# ArduinoWeatherStation.net
KiCad netlist of a schematic drawn in EAGLE
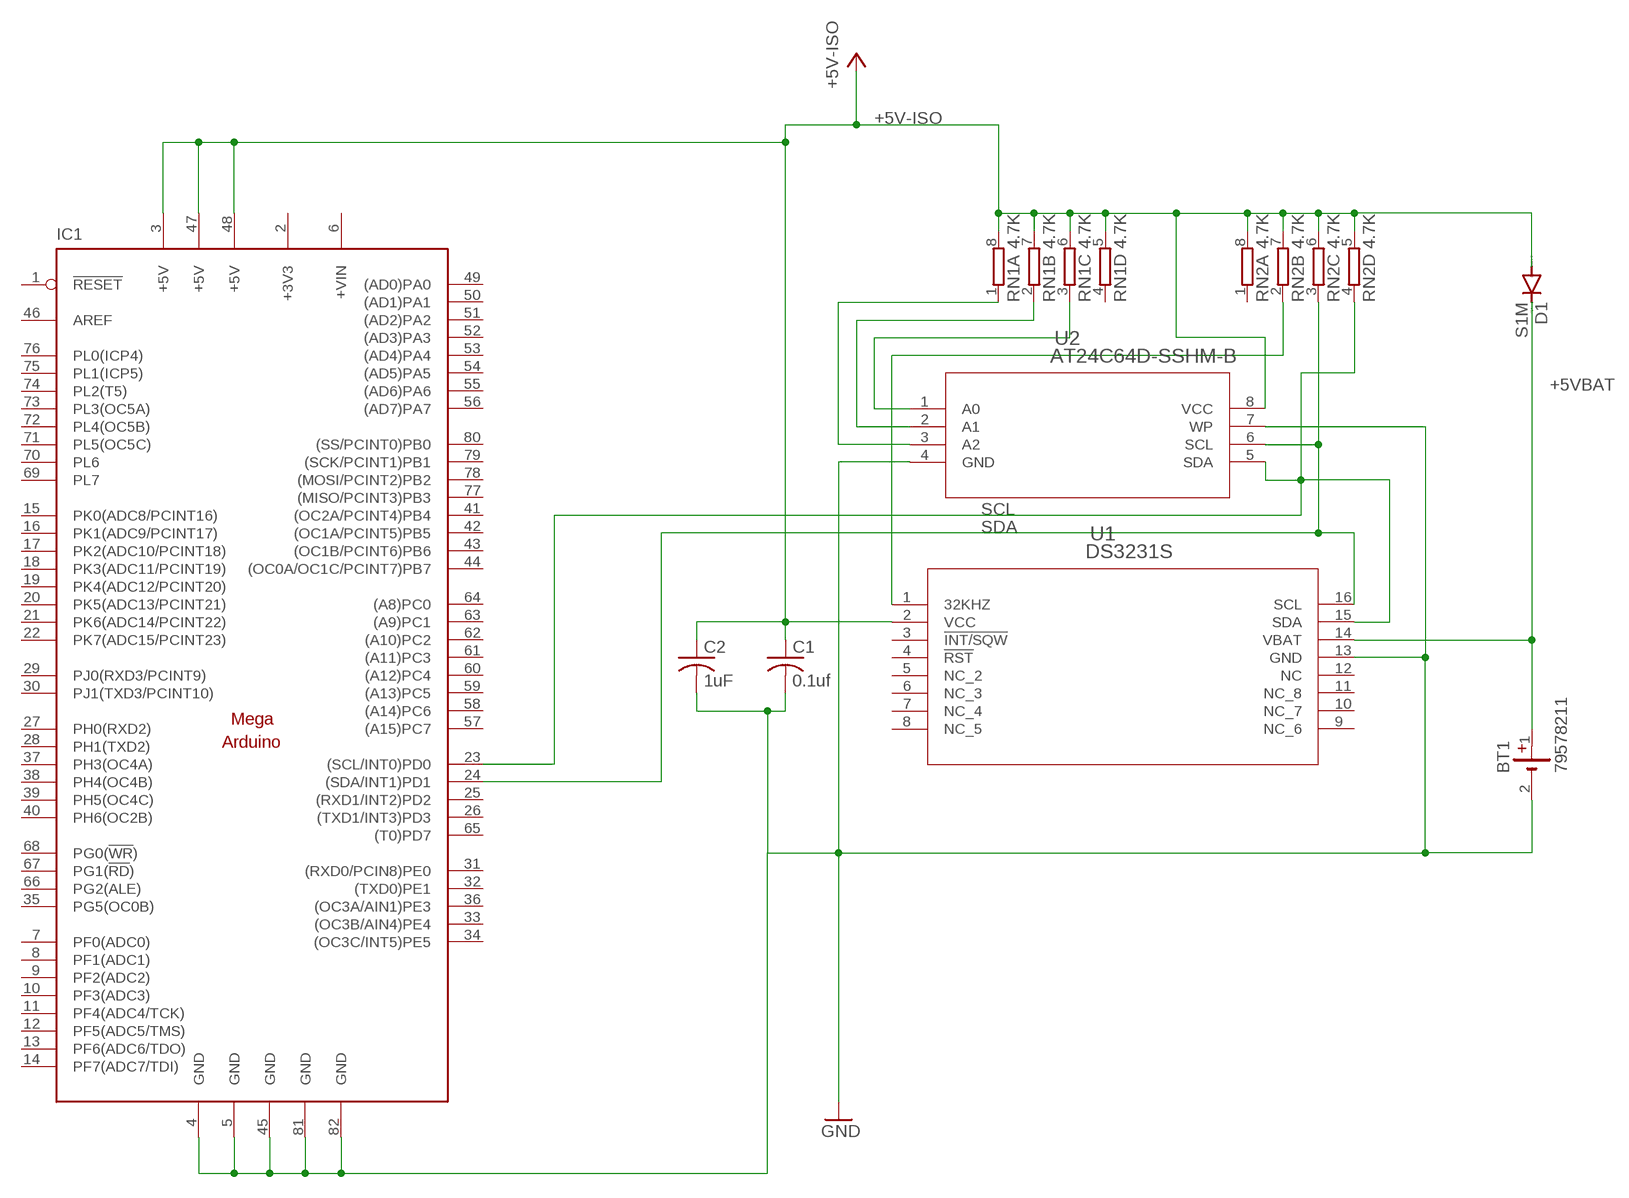
[diagram p0: schematic, sheet 1]

(export (version "E")
  (design (tool "Eeschema 10.0.6"))
  (components
    (comp (ref "BT1")
      (value "79578211")
      (footprint "eagle-import:79578211")
      (fields
        (field (name "DIGIKEY_PART_NO") "732-12330-ND")
        (field (name "MANUFACTURER") "Wurth Electronics Inc.")
        (field (name "CREATED_BY") "PCBLayout.com")
      )
      (libsource (lib "eagle-import") (part "79578211"))
    )
    (comp (ref "C1")
      (value "0.1uf")
      (footprint "eagle-import:C0603")
      (libsource (lib "eagle-import") (part "C-USC0603"))
    )
    (comp (ref "C2")
      (value "1uF")
      (footprint "eagle-import:C0603")
      (libsource (lib "eagle-import") (part "C-USC0603"))
    )
    (comp (ref "D1")
      (value "S1M")
      (footprint "eagle-import:SMA")
      (libsource (lib "eagle-import") (part "S1M"))
    )
    (comp (ref "IC1")
      (value "MEGAARDUINO_1")
      (footprint "eagle-import:MEGA_ARDUINO")
      (libsource (lib "eagle-import") (part "MEGAARDUINO_1"))
    )
    (comp (ref "RN1")
      (value "4.7K")
      (footprint "eagle-import:0603-ARC")
      (libsource (lib "eagle-import") (part "4R-N0603-ARC"))
    )
    (comp (ref "RN2")
      (value "4.7K")
      (footprint "eagle-import:0603-ARC")
      (libsource (lib "eagle-import") (part "4R-N0603-ARC"))
    )
    (comp (ref "U1")
      (value "DS3231S")
      (footprint "eagle-import:21-0042B_16")
      (libsource (lib "eagle-import") (part "DS3231S"))
    )
    (comp (ref "U2")
      (value "AT24C64D-SSHM-B")
      (footprint "eagle-import:8S1")
      (fields (field (name "MANUFACTURER_PART_NUMBER") "AT24C64DSSHMB"))
      (libsource (lib "eagle-import") (part "AT24C64D-SSHM-B"))
    )
  )
  (nets
    (net (code "1") (name "+5V-ISO") (class "Default")
      (node (ref "C1") (pin "1") (pinfunction "1_1") (pintype "passive"))
      (node (ref "C2") (pin "1") (pinfunction "1_1") (pintype "passive"))
      (node (ref "D1") (pin "A") (pinfunction "A_A") (pintype "passive"))
      (node (ref "IC1") (pin "3") (pinfunction "+5V_3") (pintype "power_in"))
      (node (ref "IC1") (pin "47") (pinfunction "+5V_47") (pintype "power_in"))
      (node (ref "IC1") (pin "48") (pinfunction "+5V_48") (pintype "power_in"))
      (node (ref "RN1") (pin "5") (pinfunction "2_5") (pintype "passive"))
      (node (ref "RN1") (pin "6") (pinfunction "2_6") (pintype "passive"))
      (node (ref "RN1") (pin "7") (pinfunction "2_7") (pintype "passive"))
      (node (ref "RN1") (pin "8") (pinfunction "2_8") (pintype "passive"))
      (node (ref "RN2") (pin "5") (pinfunction "2_5") (pintype "passive"))
      (node (ref "RN2") (pin "6") (pinfunction "2_6") (pintype "passive"))
      (node (ref "RN2") (pin "7") (pinfunction "2_7") (pintype "passive"))
      (node (ref "RN2") (pin "8") (pinfunction "2_8") (pintype "passive"))
      (node (ref "U1") (pin "2") (pinfunction "VCC_2") (pintype "power_in"))
      (node (ref "U2") (pin "8") (pinfunction "VCC_8") (pintype "power_in"))
    )
    (net (code "2") (name "/+3V3") (class "Default")
      (node (ref "IC1") (pin "2") (pinfunction "+3V3_2") (pintype "power_in"))
    )
    (net (code "3") (name "/+5VBAT") (class "Default")
      (node (ref "BT1") (pin "1") (pinfunction "+_1") (pintype "passive"))
      (node (ref "D1") (pin "C") (pinfunction "C_C") (pintype "passive"))
      (node (ref "U1") (pin "14") (pinfunction "VBAT_14") (pintype "power_in"))
    )
    (net (code "4") (name "/+VIN") (class "Default")
      (node (ref "IC1") (pin "6") (pinfunction "+VIN_6") (pintype "power_in"))
    )
    (net (code "5") (name "/SCL") (class "Default")
      (node (ref "IC1") (pin "23") (pinfunction "(SCL/INT0)PD0_23") (pintype "bidirectional"))
      (node (ref "RN2") (pin "4") (pinfunction "1_4") (pintype "passive"))
      (node (ref "U1") (pin "15") (pinfunction "SDA_15") (pintype "passive"))
      (node (ref "U2") (pin "5") (pinfunction "SDA_5") (pintype "passive"))
    )
    (net (code "6") (name "/SDA") (class "Default")
      (node (ref "IC1") (pin "24") (pinfunction "(SDA/INT1)PD1_24") (pintype "bidirectional"))
      (node (ref "RN2") (pin "3") (pinfunction "1_3") (pintype "passive"))
      (node (ref "U1") (pin "16") (pinfunction "SCL_16") (pintype "passive"))
      (node (ref "U2") (pin "6") (pinfunction "SCL_6") (pintype "input"))
    )
    (net (code "7") (name "GND") (class "Default")
      (node (ref "BT1") (pin "2") (pinfunction "-_2") (pintype "passive"))
      (node (ref "C1") (pin "2") (pinfunction "2_2") (pintype "passive"))
      (node (ref "C2") (pin "2") (pinfunction "2_2") (pintype "passive"))
      (node (ref "IC1") (pin "4") (pinfunction "GND_4") (pintype "power_in"))
      (node (ref "IC1") (pin "45") (pinfunction "GND_45") (pintype "power_in"))
      (node (ref "IC1") (pin "5") (pinfunction "GND_5") (pintype "power_in"))
      (node (ref "IC1") (pin "81") (pinfunction "GND_81") (pintype "power_in"))
      (node (ref "IC1") (pin "82") (pinfunction "GND_82") (pintype "power_in"))
      (node (ref "U1") (pin "13") (pinfunction "GND_13") (pintype "power_in"))
      (node (ref "U2") (pin "4") (pinfunction "GND_4") (pintype "power_in"))
      (node (ref "U2") (pin "7") (pinfunction "WP_7") (pintype "passive"))
    )
    (net (code "8") (name "Net-(RN1B-1)") (class "Default")
      (node (ref "RN1") (pin "2") (pinfunction "1_2") (pintype "passive"))
      (node (ref "U2") (pin "2") (pinfunction "A1_2") (pintype "input"))
    )
    (net (code "9") (name "Net-(RN1C-1)") (class "Default")
      (node (ref "RN1") (pin "3") (pinfunction "1_3") (pintype "passive"))
      (node (ref "U2") (pin "1") (pinfunction "A0_1") (pintype "input"))
    )
    (net (code "10") (name "Net-(RN2B-1)") (class "Default")
      (node (ref "RN2") (pin "2") (pinfunction "1_2") (pintype "passive"))
      (node (ref "U1") (pin "1") (pinfunction "32KHZ_1") (pintype "passive"))
    )
    (net (code "11") (name "Net-(U2-A2)") (class "Default")
      (node (ref "RN1") (pin "1") (pinfunction "1_1") (pintype "passive"))
      (node (ref "U2") (pin "3") (pinfunction "A2_3") (pintype "input"))
    )
    (net (code "12") (name "unconnected-(IC1-(A8)PC0-Pad64)") (class "Default")
      (node (ref "IC1") (pin "64") (pinfunction "(A8)PC0_64") (pintype "bidirectional"))
    )
    (net (code "13") (name "unconnected-(IC1-(A9)PC1-Pad63)") (class "Default")
      (node (ref "IC1") (pin "63") (pinfunction "(A9)PC1_63") (pintype "bidirectional"))
    )
    (net (code "14") (name "unconnected-(IC1-(A10)PC2-Pad62)") (class "Default")
      (node (ref "IC1") (pin "62") (pinfunction "(A10)PC2_62") (pintype "bidirectional"))
    )
    (net (code "15") (name "unconnected-(IC1-(A11)PC3-Pad61)") (class "Default")
      (node (ref "IC1") (pin "61") (pinfunction "(A11)PC3_61") (pintype "bidirectional"))
    )
    (net (code "16") (name "unconnected-(IC1-(A12)PC4-Pad60)") (class "Default")
      (node (ref "IC1") (pin "60") (pinfunction "(A12)PC4_60") (pintype "bidirectional"))
    )
    (net (code "17") (name "unconnected-(IC1-(A13)PC5-Pad59)") (class "Default")
      (node (ref "IC1") (pin "59") (pinfunction "(A13)PC5_59") (pintype "bidirectional"))
    )
    (net (code "18") (name "unconnected-(IC1-(A14)PC6-Pad58)") (class "Default")
      (node (ref "IC1") (pin "58") (pinfunction "(A14)PC6_58") (pintype "bidirectional"))
    )
    (net (code "19") (name "unconnected-(IC1-(A15)PC7-Pad57)") (class "Default")
      (node (ref "IC1") (pin "57") (pinfunction "(A15)PC7_57") (pintype "bidirectional"))
    )
    (net (code "20") (name "unconnected-(IC1-(AD0)PA0-Pad49)") (class "Default")
      (node (ref "IC1") (pin "49") (pinfunction "(AD0)PA0_49") (pintype "bidirectional"))
    )
    (net (code "21") (name "unconnected-(IC1-(AD1)PA1-Pad50)") (class "Default")
      (node (ref "IC1") (pin "50") (pinfunction "(AD1)PA1_50") (pintype "bidirectional"))
    )
    (net (code "22") (name "unconnected-(IC1-(AD2)PA2-Pad51)") (class "Default")
      (node (ref "IC1") (pin "51") (pinfunction "(AD2)PA2_51") (pintype "bidirectional"))
    )
    (net (code "23") (name "unconnected-(IC1-(AD3)PA3-Pad52)") (class "Default")
      (node (ref "IC1") (pin "52") (pinfunction "(AD3)PA3_52") (pintype "bidirectional"))
    )
    (net (code "24") (name "unconnected-(IC1-(AD4)PA4-Pad53)") (class "Default")
      (node (ref "IC1") (pin "53") (pinfunction "(AD4)PA4_53") (pintype "bidirectional"))
    )
    (net (code "25") (name "unconnected-(IC1-(AD5)PA5-Pad54)") (class "Default")
      (node (ref "IC1") (pin "54") (pinfunction "(AD5)PA5_54") (pintype "bidirectional"))
    )
    (net (code "26") (name "unconnected-(IC1-(AD6)PA6-Pad55)") (class "Default")
      (node (ref "IC1") (pin "55") (pinfunction "(AD6)PA6_55") (pintype "bidirectional"))
    )
    (net (code "27") (name "unconnected-(IC1-(AD7)PA7-Pad56)") (class "Default")
      (node (ref "IC1") (pin "56") (pinfunction "(AD7)PA7_56") (pintype "bidirectional"))
    )
    (net (code "28") (name "unconnected-(IC1-(MISO{slash}PCINT3)PB3-Pad77)") (class "Default")
      (node (ref "IC1") (pin "77") (pinfunction "(MISO/PCINT3)PB3_77") (pintype "bidirectional"))
    )
    (net (code "29") (name "unconnected-(IC1-(MOSI{slash}PCINT2)PB2-Pad78)") (class "Default")
      (node (ref "IC1") (pin "78") (pinfunction "(MOSI/PCINT2)PB2_78") (pintype "bidirectional"))
    )
    (net (code "30") (name "unconnected-(IC1-(OC0A{slash}OC1C{slash}PCINT7)PB7-Pad44)") (class "Default")
      (node (ref "IC1") (pin "44") (pinfunction "(OC0A/OC1C/PCINT7)PB7_44") (pintype "bidirectional"))
    )
    (net (code "31") (name "unconnected-(IC1-(OC1A{slash}PCINT5)PB5-Pad42)") (class "Default")
      (node (ref "IC1") (pin "42") (pinfunction "(OC1A/PCINT5)PB5_42") (pintype "bidirectional"))
    )
    (net (code "32") (name "unconnected-(IC1-(OC1B{slash}PCINT6)PB6-Pad43)") (class "Default")
      (node (ref "IC1") (pin "43") (pinfunction "(OC1B/PCINT6)PB6_43") (pintype "bidirectional"))
    )
    (net (code "33") (name "unconnected-(IC1-(OC2A{slash}PCINT4)PB4-Pad41)") (class "Default")
      (node (ref "IC1") (pin "41") (pinfunction "(OC2A/PCINT4)PB4_41") (pintype "bidirectional"))
    )
    (net (code "34") (name "unconnected-(IC1-(OC3A{slash}AIN1)PE3-Pad36)") (class "Default")
      (node (ref "IC1") (pin "36") (pinfunction "(OC3A/AIN1)PE3_36") (pintype "bidirectional"))
    )
    (net (code "35") (name "unconnected-(IC1-(OC3B{slash}AIN4)PE4-Pad33)") (class "Default")
      (node (ref "IC1") (pin "33") (pinfunction "(OC3B/AIN4)PE4_33") (pintype "bidirectional"))
    )
    (net (code "36") (name "unconnected-(IC1-(OC3C{slash}INT5)PE5-Pad34)") (class "Default")
      (node (ref "IC1") (pin "34") (pinfunction "(OC3C/INT5)PE5_34") (pintype "bidirectional"))
    )
    (net (code "37") (name "unconnected-(IC1-(RXD0{slash}PCIN8)PE0-Pad31)") (class "Default")
      (node (ref "IC1") (pin "31") (pinfunction "(RXD0/PCIN8)PE0_31") (pintype "bidirectional"))
    )
    (net (code "38") (name "unconnected-(IC1-(RXD1{slash}INT2)PD2-Pad25)") (class "Default")
      (node (ref "IC1") (pin "25") (pinfunction "(RXD1/INT2)PD2_25") (pintype "bidirectional"))
    )
    (net (code "39") (name "unconnected-(IC1-(SCK{slash}PCINT1)PB1-Pad79)") (class "Default")
      (node (ref "IC1") (pin "79") (pinfunction "(SCK/PCINT1)PB1_79") (pintype "bidirectional"))
    )
    (net (code "40") (name "unconnected-(IC1-(SS{slash}PCINT0)PB0-Pad80)") (class "Default")
      (node (ref "IC1") (pin "80") (pinfunction "(SS/PCINT0)PB0_80") (pintype "bidirectional"))
    )
    (net (code "41") (name "unconnected-(IC1-(T0)PD7-Pad65)") (class "Default")
      (node (ref "IC1") (pin "65") (pinfunction "(T0)PD7_65") (pintype "bidirectional"))
    )
    (net (code "42") (name "unconnected-(IC1-(TXD0)PE1-Pad32)") (class "Default")
      (node (ref "IC1") (pin "32") (pinfunction "(TXD0)PE1_32") (pintype "bidirectional"))
    )
    (net (code "43") (name "unconnected-(IC1-(TXD1{slash}INT3)PD3-Pad26)") (class "Default")
      (node (ref "IC1") (pin "26") (pinfunction "(TXD1/INT3)PD3_26") (pintype "bidirectional"))
    )
    (net (code "44") (name "unconnected-(IC1-AREF-Pad46)") (class "Default")
      (node (ref "IC1") (pin "46") (pinfunction "AREF_46") (pintype "bidirectional"))
    )
    (net (code "45") (name "unconnected-(IC1-PF0(ADC0)-Pad7)") (class "Default")
      (node (ref "IC1") (pin "7") (pinfunction "PF0(ADC0)_7") (pintype "bidirectional"))
    )
    (net (code "46") (name "unconnected-(IC1-PF1(ADC1)-Pad8)") (class "Default")
      (node (ref "IC1") (pin "8") (pinfunction "PF1(ADC1)_8") (pintype "bidirectional"))
    )
    (net (code "47") (name "unconnected-(IC1-PF2(ADC2)-Pad9)") (class "Default")
      (node (ref "IC1") (pin "9") (pinfunction "PF2(ADC2)_9") (pintype "bidirectional"))
    )
    (net (code "48") (name "unconnected-(IC1-PF3(ADC3)-Pad10)") (class "Default")
      (node (ref "IC1") (pin "10") (pinfunction "PF3(ADC3)_10") (pintype "bidirectional"))
    )
    (net (code "49") (name "unconnected-(IC1-PF4(ADC4{slash}TCK)-Pad11)") (class "Default")
      (node (ref "IC1") (pin "11") (pinfunction "PF4(ADC4/TCK)_11") (pintype "bidirectional"))
    )
    (net (code "50") (name "unconnected-(IC1-PF5(ADC5{slash}TMS)-Pad12)") (class "Default")
      (node (ref "IC1") (pin "12") (pinfunction "PF5(ADC5/TMS)_12") (pintype "bidirectional"))
    )
    (net (code "51") (name "unconnected-(IC1-PF6(ADC6{slash}TDO)-Pad13)") (class "Default")
      (node (ref "IC1") (pin "13") (pinfunction "PF6(ADC6/TDO)_13") (pintype "bidirectional"))
    )
    (net (code "52") (name "unconnected-(IC1-PF7(ADC7{slash}TDI)-Pad14)") (class "Default")
      (node (ref "IC1") (pin "14") (pinfunction "PF7(ADC7/TDI)_14") (pintype "bidirectional"))
    )
    (net (code "53") (name "unconnected-(IC1-PG0(~{WR})-Pad68)") (class "Default")
      (node (ref "IC1") (pin "68") (pinfunction "PG0(~{WR})_68") (pintype "bidirectional"))
    )
    (net (code "54") (name "unconnected-(IC1-PG1(~{RD})-Pad67)") (class "Default")
      (node (ref "IC1") (pin "67") (pinfunction "PG1(~{RD})_67") (pintype "bidirectional"))
    )
    (net (code "55") (name "unconnected-(IC1-PG2(ALE)-Pad66)") (class "Default")
      (node (ref "IC1") (pin "66") (pinfunction "PG2(ALE)_66") (pintype "bidirectional"))
    )
    (net (code "56") (name "unconnected-(IC1-PG5(OC0B)-Pad35)") (class "Default")
      (node (ref "IC1") (pin "35") (pinfunction "PG5(OC0B)_35") (pintype "bidirectional"))
    )
    (net (code "57") (name "unconnected-(IC1-PH0(RXD2)-Pad27)") (class "Default")
      (node (ref "IC1") (pin "27") (pinfunction "PH0(RXD2)_27") (pintype "bidirectional"))
    )
    (net (code "58") (name "unconnected-(IC1-PH1(TXD2)-Pad28)") (class "Default")
      (node (ref "IC1") (pin "28") (pinfunction "PH1(TXD2)_28") (pintype "bidirectional"))
    )
    (net (code "59") (name "unconnected-(IC1-PH3(OC4A)-Pad37)") (class "Default")
      (node (ref "IC1") (pin "37") (pinfunction "PH3(OC4A)_37") (pintype "bidirectional"))
    )
    (net (code "60") (name "unconnected-(IC1-PH4(OC4B)-Pad38)") (class "Default")
      (node (ref "IC1") (pin "38") (pinfunction "PH4(OC4B)_38") (pintype "bidirectional"))
    )
    (net (code "61") (name "unconnected-(IC1-PH5(OC4C)-Pad39)") (class "Default")
      (node (ref "IC1") (pin "39") (pinfunction "PH5(OC4C)_39") (pintype "bidirectional"))
    )
    (net (code "62") (name "unconnected-(IC1-PH6(OC2B)-Pad40)") (class "Default")
      (node (ref "IC1") (pin "40") (pinfunction "PH6(OC2B)_40") (pintype "bidirectional"))
    )
    (net (code "63") (name "unconnected-(IC1-PJ0(RXD3{slash}PCINT9)-Pad29)") (class "Default")
      (node (ref "IC1") (pin "29") (pinfunction "PJ0(RXD3/PCINT9)_29") (pintype "bidirectional"))
    )
    (net (code "64") (name "unconnected-(IC1-PJ1(TXD3{slash}PCINT10)-Pad30)") (class "Default")
      (node (ref "IC1") (pin "30") (pinfunction "PJ1(TXD3/PCINT10)_30") (pintype "bidirectional"))
    )
    (net (code "65") (name "unconnected-(IC1-PK0(ADC8{slash}PCINT16)-Pad15)") (class "Default")
      (node (ref "IC1") (pin "15") (pinfunction "PK0(ADC8/PCINT16)_15") (pintype "bidirectional"))
    )
    (net (code "66") (name "unconnected-(IC1-PK1(ADC9{slash}PCINT17)-Pad16)") (class "Default")
      (node (ref "IC1") (pin "16") (pinfunction "PK1(ADC9/PCINT17)_16") (pintype "bidirectional"))
    )
    (net (code "67") (name "unconnected-(IC1-PK2(ADC10{slash}PCINT18)-Pad17)") (class "Default")
      (node (ref "IC1") (pin "17") (pinfunction "PK2(ADC10/PCINT18)_17") (pintype "bidirectional"))
    )
    (net (code "68") (name "unconnected-(IC1-PK3(ADC11{slash}PCINT19)-Pad18)") (class "Default")
      (node (ref "IC1") (pin "18") (pinfunction "PK3(ADC11/PCINT19)_18") (pintype "bidirectional"))
    )
    (net (code "69") (name "unconnected-(IC1-PK4(ADC12{slash}PCINT20)-Pad19)") (class "Default")
      (node (ref "IC1") (pin "19") (pinfunction "PK4(ADC12/PCINT20)_19") (pintype "bidirectional"))
    )
    (net (code "70") (name "unconnected-(IC1-PK5(ADC13{slash}PCINT21)-Pad20)") (class "Default")
      (node (ref "IC1") (pin "20") (pinfunction "PK5(ADC13/PCINT21)_20") (pintype "bidirectional"))
    )
    (net (code "71") (name "unconnected-(IC1-PK6(ADC14{slash}PCINT22)-Pad21)") (class "Default")
      (node (ref "IC1") (pin "21") (pinfunction "PK6(ADC14/PCINT22)_21") (pintype "bidirectional"))
    )
    (net (code "72") (name "unconnected-(IC1-PK7(ADC15{slash}PCINT23)-Pad22)") (class "Default")
      (node (ref "IC1") (pin "22") (pinfunction "PK7(ADC15/PCINT23)_22") (pintype "bidirectional"))
    )
    (net (code "73") (name "unconnected-(IC1-PL0(ICP4)-Pad76)") (class "Default")
      (node (ref "IC1") (pin "76") (pinfunction "PL0(ICP4)_76") (pintype "bidirectional"))
    )
    (net (code "74") (name "unconnected-(IC1-PL1(ICP5)-Pad75)") (class "Default")
      (node (ref "IC1") (pin "75") (pinfunction "PL1(ICP5)_75") (pintype "bidirectional"))
    )
    (net (code "75") (name "unconnected-(IC1-PL2(T5)-Pad74)") (class "Default")
      (node (ref "IC1") (pin "74") (pinfunction "PL2(T5)_74") (pintype "bidirectional"))
    )
    (net (code "76") (name "unconnected-(IC1-PL3(OC5A)-Pad73)") (class "Default")
      (node (ref "IC1") (pin "73") (pinfunction "PL3(OC5A)_73") (pintype "bidirectional"))
    )
    (net (code "77") (name "unconnected-(IC1-PL4(OC5B)-Pad72)") (class "Default")
      (node (ref "IC1") (pin "72") (pinfunction "PL4(OC5B)_72") (pintype "bidirectional"))
    )
    (net (code "78") (name "unconnected-(IC1-PL5(OC5C)-Pad71)") (class "Default")
      (node (ref "IC1") (pin "71") (pinfunction "PL5(OC5C)_71") (pintype "bidirectional"))
    )
    (net (code "79") (name "unconnected-(IC1-PL6-Pad70)") (class "Default")
      (node (ref "IC1") (pin "70") (pinfunction "PL6_70") (pintype "bidirectional"))
    )
    (net (code "80") (name "unconnected-(IC1-PL7-Pad69)") (class "Default")
      (node (ref "IC1") (pin "69") (pinfunction "PL7_69") (pintype "bidirectional"))
    )
    (net (code "81") (name "unconnected-(IC1-~{RESET}-Pad1)") (class "Default")
      (node (ref "IC1") (pin "1") (pinfunction "~{RESET}_1") (pintype "bidirectional"))
    )
    (net (code "82") (name "unconnected-(RN1D-1-Pad4)") (class "Default")
      (node (ref "RN1") (pin "4") (pinfunction "1_4") (pintype "passive"))
    )
    (net (code "83") (name "unconnected-(RN2-Pad1)") (class "Default")
      (node (ref "RN2") (pin "1") (pinfunction "1_1") (pintype "passive"))
    )
    (net (code "84") (name "unconnected-(U1-NC-Pad12)") (class "Default")
      (node (ref "U1") (pin "12") (pinfunction "NC_12") (pintype "passive"))
    )
    (net (code "85") (name "unconnected-(U1-NC_2-Pad5)") (class "Default")
      (node (ref "U1") (pin "5") (pinfunction "NC_2_5") (pintype "passive"))
    )
    (net (code "86") (name "unconnected-(U1-NC_3-Pad6)") (class "Default")
      (node (ref "U1") (pin "6") (pinfunction "NC_3_6") (pintype "passive"))
    )
    (net (code "87") (name "unconnected-(U1-NC_4-Pad7)") (class "Default")
      (node (ref "U1") (pin "7") (pinfunction "NC_4_7") (pintype "passive"))
    )
    (net (code "88") (name "unconnected-(U1-NC_5-Pad8)") (class "Default")
      (node (ref "U1") (pin "8") (pinfunction "NC_5_8") (pintype "passive"))
    )
    (net (code "89") (name "unconnected-(U1-NC_6-Pad9)") (class "Default")
      (node (ref "U1") (pin "9") (pinfunction "NC_6_9") (pintype "passive"))
    )
    (net (code "90") (name "unconnected-(U1-NC_7-Pad10)") (class "Default")
      (node (ref "U1") (pin "10") (pinfunction "NC_7_10") (pintype "passive"))
    )
    (net (code "91") (name "unconnected-(U1-NC_8-Pad11)") (class "Default")
      (node (ref "U1") (pin "11") (pinfunction "NC_8_11") (pintype "passive"))
    )
    (net (code "92") (name "unconnected-(U1-~{INT{slash}SQW}-Pad3)") (class "Default")
      (node (ref "U1") (pin "3") (pinfunction "~{INT/SQW}_3") (pintype "passive"))
    )
    (net (code "93") (name "unconnected-(U1-~{RST}-Pad4)") (class "Default")
      (node (ref "U1") (pin "4") (pinfunction "~{RST}_4") (pintype "passive"))
    )
  )
)
